# Audio-Amplifier-RickAndersen.net
KiCad netlist of a schematic drawn in EAGLE
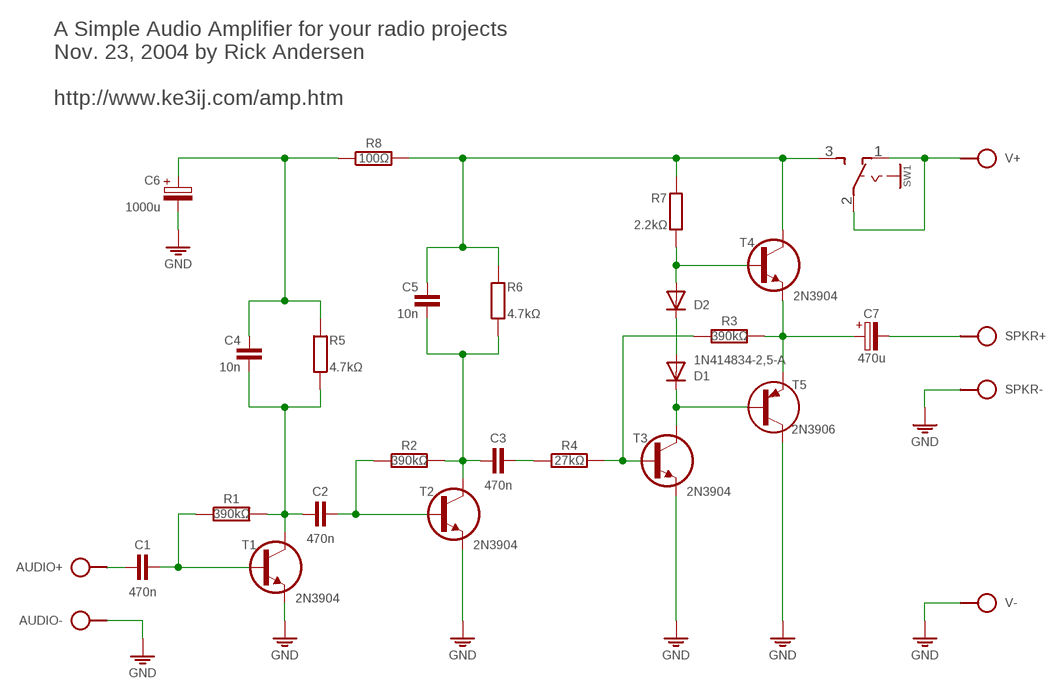
[diagram p0: schematic, sheet 1]

(export (version "E")
  (design (tool "Eeschema 10.0.6"))
  (components
    (comp (ref "AUDIO")
      (value "SPAD+-+-")
      (footprint "eagle-import:SPAD+-")
      (libsource (lib "eagle-import") (part "SPAD+-+-"))
    )
    (comp (ref "C1")
      (value "470n")
      (footprint "eagle-import:C050-020X044")
      (libsource (lib "eagle-import") (part "C050-020X044"))
    )
    (comp (ref "C2")
      (value "470n")
      (footprint "eagle-import:C050-020X044")
      (libsource (lib "eagle-import") (part "C050-020X044"))
    )
    (comp (ref "C3")
      (value "470n")
      (footprint "eagle-import:C050-020X044")
      (libsource (lib "eagle-import") (part "C050-020X044"))
    )
    (comp (ref "C4")
      (value "10n")
      (footprint "eagle-import:C025-015X024")
      (libsource (lib "eagle-import") (part "C025-015X024"))
    )
    (comp (ref "C5")
      (value "10n")
      (footprint "eagle-import:C025-015X024")
      (libsource (lib "eagle-import") (part "C025-015X024"))
    )
    (comp (ref "C6")
      (value "1000u")
      (footprint "eagle-import:E5-6")
      (libsource (lib "eagle-import") (part "CPOLE5-6"))
    )
    (comp (ref "C7")
      (value "470u")
      (footprint "eagle-import:E5-6")
      (libsource (lib "eagle-import") (part "CPOLE5-6"))
    )
    (comp (ref "D1")
      (value "1N414834-2,5-A")
      (footprint "eagle-import:DO34-2,5-A")
      (libsource (lib "eagle-import") (part "1N414834-2,5-A"))
    )
    (comp (ref "D2")
      (value "1N414834-5V")
      (footprint "eagle-import:DO34-5V")
      (libsource (lib "eagle-import") (part "1N414834-5V"))
    )
    (comp (ref "R1")
      (value "390kΩ")
      (footprint "eagle-import:0202_7-V")
      (libsource (lib "eagle-import") (part "R-H0202/7-V"))
    )
    (comp (ref "R2")
      (value "390kΩ")
      (footprint "eagle-import:0202_7-V")
      (libsource (lib "eagle-import") (part "R-H0202/7-V"))
    )
    (comp (ref "R3")
      (value "390kΩ")
      (footprint "eagle-import:0202_7-V")
      (libsource (lib "eagle-import") (part "R-H0202/7-V"))
    )
    (comp (ref "R4")
      (value "27kΩ")
      (footprint "eagle-import:0202_7-V")
      (libsource (lib "eagle-import") (part "R-H0202/7-V"))
    )
    (comp (ref "R5")
      (value "4.7kΩ")
      (footprint "eagle-import:0202_7-V")
      (libsource (lib "eagle-import") (part "R0202/7-V"))
    )
    (comp (ref "R6")
      (value "4.7kΩ")
      (footprint "eagle-import:0202_7-V")
      (libsource (lib "eagle-import") (part "R0202/7-V"))
    )
    (comp (ref "R7")
      (value "2.2kΩ")
      (footprint "eagle-import:0202_7")
      (libsource (lib "eagle-import") (part "R0202/7"))
    )
    (comp (ref "R8")
      (value "100Ω")
      (footprint "eagle-import:0202_7")
      (libsource (lib "eagle-import") (part "R-H0202/7"))
    )
    (comp (ref "SPKR")
      (value "SPAD+-+-")
      (footprint "eagle-import:SPAD+-")
      (libsource (lib "eagle-import") (part "SPAD+-+-"))
    )
    (comp (ref "SW1")
      (value "SL-SW-1P-2T-H")
      (footprint "eagle-import:SLSW-1P2T-H")
      (libsource (lib "eagle-import") (part "SL-SW-1P-2T-H"))
    )
    (comp (ref "T1")
      (value "2N3904")
      (footprint "eagle-import:TO92")
      (libsource (lib "eagle-import") (part "2N3904"))
    )
    (comp (ref "T2")
      (value "2N3904")
      (footprint "eagle-import:TO92")
      (libsource (lib "eagle-import") (part "2N3904"))
    )
    (comp (ref "T3")
      (value "2N3904")
      (footprint "eagle-import:TO92")
      (libsource (lib "eagle-import") (part "2N3904"))
    )
    (comp (ref "T4")
      (value "2N3904")
      (footprint "eagle-import:TO92")
      (libsource (lib "eagle-import") (part "2N3904"))
    )
    (comp (ref "T5")
      (value "2N3906")
      (footprint "eagle-import:TO92")
      (libsource (lib "eagle-import") (part "2N3906"))
    )
    (comp (ref "V+")
      (value "SPAD")
      (footprint "eagle-import:SPAD")
      (libsource (lib "eagle-import") (part "SPAD"))
    )
    (comp (ref "V-")
      (value "SPAD")
      (footprint "eagle-import:SPAD")
      (libsource (lib "eagle-import") (part "SPAD"))
    )
  )
  (nets
    (net (code "1") (name "GND") (class "Default")
      (node (ref "AUDIO") (pin "1") (pinfunction "P$1_1") (pintype "passive"))
      (node (ref "C6") (pin "-") (pinfunction "-_-") (pintype "passive"))
      (node (ref "SPKR") (pin "1") (pinfunction "P$1_1") (pintype "passive"))
      (node (ref "T1") (pin "1") (pinfunction "E_1") (pintype "passive"))
      (node (ref "T2") (pin "1") (pinfunction "E_1") (pintype "passive"))
      (node (ref "T3") (pin "1") (pinfunction "E_1") (pintype "passive"))
      (node (ref "T5") (pin "3") (pinfunction "C_3") (pintype "passive"))
      (node (ref "V-") (pin "1") (pinfunction "P$1_1") (pintype "passive"))
    )
    (net (code "2") (name "Net-(AUDIOA-P$1)") (class "Default")
      (node (ref "AUDIO") (pin "2") (pinfunction "P$1_2") (pintype "passive"))
      (node (ref "C1") (pin "1") (pinfunction "1_1") (pintype "passive"))
    )
    (net (code "3") (name "Net-(C3-Pad2)") (class "Default")
      (node (ref "C3") (pin "2") (pinfunction "2_2") (pintype "passive"))
      (node (ref "R4") (pin "1") (pinfunction "1_1") (pintype "passive"))
    )
    (net (code "4") (name "Net-(C4-Pad1)") (class "Default")
      (node (ref "C4") (pin "1") (pinfunction "1_1") (pintype "passive"))
      (node (ref "C6") (pin "+") (pinfunction "+_+") (pintype "passive"))
      (node (ref "R5") (pin "1") (pinfunction "1_1") (pintype "passive"))
      (node (ref "R8") (pin "1") (pinfunction "1_1") (pintype "passive"))
    )
    (net (code "5") (name "Net-(D1-PadA)") (class "Default")
      (node (ref "D1") (pin "A") (pinfunction "A_A") (pintype "passive"))
      (node (ref "D2") (pin "C") (pinfunction "C_C") (pintype "passive"))
    )
    (net (code "6") (name "Net-(SPKRA-P$1)") (class "Default")
      (node (ref "C7") (pin "-") (pinfunction "-_-") (pintype "passive"))
      (node (ref "SPKR") (pin "2") (pinfunction "P$1_2") (pintype "passive"))
    )
    (net (code "7") (name "Net-(SW1-O)") (class "Default")
      (node (ref "SW1") (pin "1") (pinfunction "O_1") (pintype "passive"))
      (node (ref "SW1") (pin "2") (pinfunction "P_2") (pintype "passive"))
      (node (ref "V+") (pin "1") (pinfunction "P$1_1") (pintype "passive"))
    )
    (net (code "8") (name "Net-(SW1-S)") (class "Default")
      (node (ref "C5") (pin "1") (pinfunction "1_1") (pintype "passive"))
      (node (ref "R6") (pin "1") (pinfunction "1_1") (pintype "passive"))
      (node (ref "R7") (pin "1") (pinfunction "1_1") (pintype "passive"))
      (node (ref "R8") (pin "2") (pinfunction "2_2") (pintype "passive"))
      (node (ref "SW1") (pin "3") (pinfunction "S_3") (pintype "passive"))
      (node (ref "T4") (pin "3") (pinfunction "C_3") (pintype "passive"))
    )
    (net (code "9") (name "Net-(T1-B)") (class "Default")
      (node (ref "C1") (pin "2") (pinfunction "2_2") (pintype "passive"))
      (node (ref "R1") (pin "1") (pinfunction "1_1") (pintype "passive"))
      (node (ref "T1") (pin "2") (pinfunction "B_2") (pintype "passive"))
    )
    (net (code "10") (name "Net-(T1-C)") (class "Default")
      (node (ref "C2") (pin "1") (pinfunction "1_1") (pintype "passive"))
      (node (ref "C4") (pin "2") (pinfunction "2_2") (pintype "passive"))
      (node (ref "R1") (pin "2") (pinfunction "2_2") (pintype "passive"))
      (node (ref "R5") (pin "2") (pinfunction "2_2") (pintype "passive"))
      (node (ref "T1") (pin "3") (pinfunction "C_3") (pintype "passive"))
    )
    (net (code "11") (name "Net-(T2-B)") (class "Default")
      (node (ref "C2") (pin "2") (pinfunction "2_2") (pintype "passive"))
      (node (ref "R2") (pin "1") (pinfunction "1_1") (pintype "passive"))
      (node (ref "T2") (pin "2") (pinfunction "B_2") (pintype "passive"))
    )
    (net (code "12") (name "Net-(T2-C)") (class "Default")
      (node (ref "C3") (pin "1") (pinfunction "1_1") (pintype "passive"))
      (node (ref "C5") (pin "2") (pinfunction "2_2") (pintype "passive"))
      (node (ref "R2") (pin "2") (pinfunction "2_2") (pintype "passive"))
      (node (ref "R6") (pin "2") (pinfunction "2_2") (pintype "passive"))
      (node (ref "T2") (pin "3") (pinfunction "C_3") (pintype "passive"))
    )
    (net (code "13") (name "Net-(T3-B)") (class "Default")
      (node (ref "R3") (pin "1") (pinfunction "1_1") (pintype "passive"))
      (node (ref "R4") (pin "2") (pinfunction "2_2") (pintype "passive"))
      (node (ref "T3") (pin "2") (pinfunction "B_2") (pintype "passive"))
    )
    (net (code "14") (name "Net-(T3-C)") (class "Default")
      (node (ref "D1") (pin "C") (pinfunction "C_C") (pintype "passive"))
      (node (ref "T3") (pin "3") (pinfunction "C_3") (pintype "passive"))
      (node (ref "T5") (pin "2") (pinfunction "B_2") (pintype "passive"))
    )
    (net (code "15") (name "Net-(T4-B)") (class "Default")
      (node (ref "D2") (pin "A") (pinfunction "A_A") (pintype "passive"))
      (node (ref "R7") (pin "2") (pinfunction "2_2") (pintype "passive"))
      (node (ref "T4") (pin "2") (pinfunction "B_2") (pintype "passive"))
    )
    (net (code "16") (name "Net-(T4-E)") (class "Default")
      (node (ref "C7") (pin "+") (pinfunction "+_+") (pintype "passive"))
      (node (ref "R3") (pin "2") (pinfunction "2_2") (pintype "passive"))
      (node (ref "T4") (pin "1") (pinfunction "E_1") (pintype "passive"))
      (node (ref "T5") (pin "1") (pinfunction "E_1") (pintype "passive"))
    )
  )
)
